# SchlafKindleinSchlaf.net
KiCad netlist of a schematic drawn in EAGLE
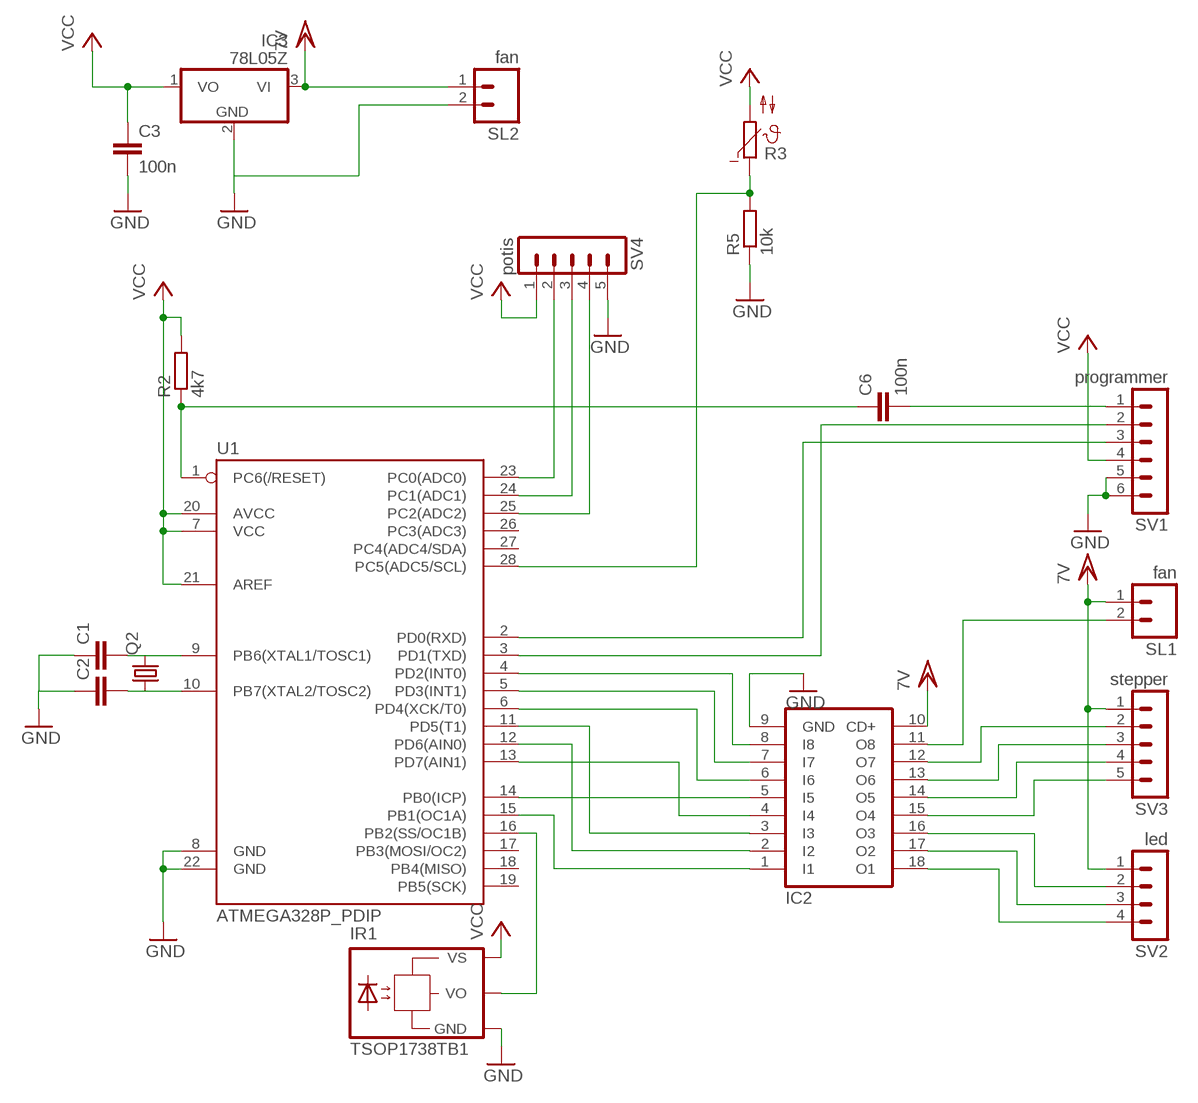
[diagram p0: schematic, sheet 1]

(export (version "E")
  (design (tool "Eeschema 10.0.6"))
  (components
    (comp (ref "C1")
      (value "C2.5/2")
      (footprint "eagle-import:C2.5-2")
      (libsource (lib "eagle-import") (part "C2.5/2"))
    )
    (comp (ref "C2")
      (value "C2.5/2")
      (footprint "eagle-import:C2.5-2")
      (libsource (lib "eagle-import") (part "C2.5/2"))
    )
    (comp (ref "C3")
      (value "100n")
      (footprint "eagle-import:C2.5-2")
      (libsource (lib "eagle-import") (part "C2.5/2"))
    )
    (comp (ref "C6")
      (value "100n")
      (footprint "eagle-import:C2.5-2")
      (libsource (lib "eagle-import") (part "C2.5/2"))
    )
    (comp (ref "IC2")
      (value "ULN2803A")
      (footprint "eagle-import:DIL18")
      (libsource (lib "eagle-import") (part "ULN2803A"))
    )
    (comp (ref "IC3")
      (value "78L05Z")
      (footprint "eagle-import:TO92")
      (libsource (lib "eagle-import") (part "78ZL05"))
    )
    (comp (ref "IR1")
      (value "TSOP1738TB1")
      (footprint "eagle-import:TSOP17_TB1")
      (libsource (lib "eagle-import") (part "TSOP17TB138"))
    )
    (comp (ref "Q2")
      (value "CRYSTALHC49S")
      (footprint "eagle-import:HC49_S")
      (libsource (lib "eagle-import") (part "CRYSTALHC49S"))
    )
    (comp (ref "R2")
      (value "4k7")
      (footprint "eagle-import:0207_7")
      (libsource (lib "eagle-import") (part "R-EU_0207/7"))
    )
    (comp (ref "R3")
      (value "NTC640")
      (footprint "eagle-import:P640")
      (libsource (lib "eagle-import") (part "NTC640"))
    )
    (comp (ref "R5")
      (value "10k")
      (footprint "eagle-import:0207_7")
      (libsource (lib "eagle-import") (part "R-EU_0207/7"))
    )
    (comp (ref "SL1")
      (value "fan")
      (footprint "eagle-import:02PA")
      (libsource (lib "eagle-import") (part "MA02"))
    )
    (comp (ref "SL2")
      (value "fan")
      (footprint "eagle-import:02PA")
      (libsource (lib "eagle-import") (part "MA02"))
    )
    (comp (ref "SV1")
      (value "programmer")
      (footprint "eagle-import:MA06-1")
      (libsource (lib "eagle-import") (part "MA06-1"))
    )
    (comp (ref "SV2")
      (value "led")
      (footprint "eagle-import:MA04-1")
      (libsource (lib "eagle-import") (part "MA04-1"))
    )
    (comp (ref "SV3")
      (value "stepper")
      (footprint "eagle-import:MA05-1")
      (libsource (lib "eagle-import") (part "MA05-1"))
    )
    (comp (ref "SV4")
      (value "potis")
      (footprint "eagle-import:MA05-1")
      (libsource (lib "eagle-import") (part "MA05-1"))
    )
    (comp (ref "U1")
      (value "ATMEGA328P_PDIP")
      (footprint "eagle-import:DIL28-3")
      (libsource (lib "eagle-import") (part "ATMEGA328P_PDIP"))
    )
  )
  (nets
    (net (code "1") (name "7V") (class "Default")
      (node (ref "IC2") (pin "10") (pinfunction "CD+_10") (pintype "passive"))
      (node (ref "IC3") (pin "3") (pinfunction "VI_3") (pintype "input"))
      (node (ref "SL1") (pin "1") (pinfunction "1_1") (pintype "passive"))
      (node (ref "SL2") (pin "1") (pinfunction "1_1") (pintype "passive"))
      (node (ref "SV2") (pin "1") (pinfunction "1_1") (pintype "passive"))
      (node (ref "SV3") (pin "1") (pinfunction "1_1") (pintype "passive"))
    )
    (net (code "2") (name "GND") (class "Default")
      (node (ref "C1") (pin "1") (pinfunction "1_1") (pintype "passive"))
      (node (ref "C2") (pin "1") (pinfunction "1_1") (pintype "passive"))
      (node (ref "C3") (pin "2") (pinfunction "2_2") (pintype "passive"))
      (node (ref "IC2") (pin "9") (pinfunction "GND_9") (pintype "power_in"))
      (node (ref "IC3") (pin "2") (pinfunction "GND_2") (pintype "passive"))
      (node (ref "IR1") (pin "GND") (pinfunction "GND_GND") (pintype "power_in"))
      (node (ref "R5") (pin "1") (pinfunction "1_1") (pintype "passive"))
      (node (ref "SL2") (pin "2") (pinfunction "2_2") (pintype "passive"))
      (node (ref "SV1") (pin "5") (pinfunction "5_5") (pintype "passive"))
      (node (ref "SV1") (pin "6") (pinfunction "6_6") (pintype "passive"))
      (node (ref "SV4") (pin "5") (pinfunction "5_5") (pintype "passive"))
      (node (ref "U1") (pin "22") (pinfunction "GND_22") (pintype "bidirectional"))
      (node (ref "U1") (pin "8") (pinfunction "GND_8") (pintype "bidirectional"))
    )
    (net (code "3") (name "Net-(C6-Pad2)") (class "Default")
      (node (ref "C6") (pin "2") (pinfunction "2_2") (pintype "passive"))
      (node (ref "SV1") (pin "1") (pinfunction "1_1") (pintype "passive"))
    )
    (net (code "4") (name "Net-(IC2-I1)") (class "Default")
      (node (ref "IC2") (pin "1") (pinfunction "I1_1") (pintype "input"))
      (node (ref "U1") (pin "15") (pinfunction "PB1(OC1A)_15") (pintype "bidirectional"))
    )
    (net (code "5") (name "Net-(IC2-I2)") (class "Default")
      (node (ref "IC2") (pin "2") (pinfunction "I2_2") (pintype "input"))
      (node (ref "U1") (pin "12") (pinfunction "PD6(AIN0)_12") (pintype "bidirectional"))
    )
    (net (code "6") (name "Net-(IC2-I3)") (class "Default")
      (node (ref "IC2") (pin "3") (pinfunction "I3_3") (pintype "input"))
      (node (ref "U1") (pin "11") (pinfunction "PD5(T1)_11") (pintype "bidirectional"))
    )
    (net (code "7") (name "Net-(IC2-I4)") (class "Default")
      (node (ref "IC2") (pin "4") (pinfunction "I4_4") (pintype "input"))
      (node (ref "U1") (pin "13") (pinfunction "PD7(AIN1)_13") (pintype "bidirectional"))
    )
    (net (code "8") (name "Net-(IC2-I5)") (class "Default")
      (node (ref "IC2") (pin "5") (pinfunction "I5_5") (pintype "input"))
      (node (ref "U1") (pin "14") (pinfunction "PB0(ICP)_14") (pintype "bidirectional"))
    )
    (net (code "9") (name "Net-(IC2-I6)") (class "Default")
      (node (ref "IC2") (pin "6") (pinfunction "I6_6") (pintype "input"))
      (node (ref "U1") (pin "6") (pinfunction "PD4(XCK/T0)_6") (pintype "bidirectional"))
    )
    (net (code "10") (name "Net-(IC2-I7)") (class "Default")
      (node (ref "IC2") (pin "7") (pinfunction "I7_7") (pintype "input"))
      (node (ref "U1") (pin "5") (pinfunction "PD3(INT1)_5") (pintype "bidirectional"))
    )
    (net (code "11") (name "Net-(IC2-I8)") (class "Default")
      (node (ref "IC2") (pin "8") (pinfunction "I8_8") (pintype "input"))
      (node (ref "U1") (pin "4") (pinfunction "PD2(INT0)_4") (pintype "bidirectional"))
    )
    (net (code "12") (name "Net-(IC2-O1)") (class "Default")
      (node (ref "IC2") (pin "18") (pinfunction "O1_18") (pintype "open_collector"))
      (node (ref "SV2") (pin "4") (pinfunction "4_4") (pintype "passive"))
    )
    (net (code "13") (name "Net-(IC2-O2)") (class "Default")
      (node (ref "IC2") (pin "17") (pinfunction "O2_17") (pintype "open_collector"))
      (node (ref "SV2") (pin "3") (pinfunction "3_3") (pintype "passive"))
    )
    (net (code "14") (name "Net-(IC2-O3)") (class "Default")
      (node (ref "IC2") (pin "16") (pinfunction "O3_16") (pintype "open_collector"))
      (node (ref "SV2") (pin "2") (pinfunction "2_2") (pintype "passive"))
    )
    (net (code "15") (name "Net-(IC2-O4)") (class "Default")
      (node (ref "IC2") (pin "15") (pinfunction "O4_15") (pintype "open_collector"))
      (node (ref "SV3") (pin "5") (pinfunction "5_5") (pintype "passive"))
    )
    (net (code "16") (name "Net-(IC2-O5)") (class "Default")
      (node (ref "IC2") (pin "14") (pinfunction "O5_14") (pintype "open_collector"))
      (node (ref "SV3") (pin "4") (pinfunction "4_4") (pintype "passive"))
    )
    (net (code "17") (name "Net-(IC2-O6)") (class "Default")
      (node (ref "IC2") (pin "13") (pinfunction "O6_13") (pintype "open_collector"))
      (node (ref "SV3") (pin "3") (pinfunction "3_3") (pintype "passive"))
    )
    (net (code "18") (name "Net-(IC2-O7)") (class "Default")
      (node (ref "IC2") (pin "12") (pinfunction "O7_12") (pintype "open_collector"))
      (node (ref "SV3") (pin "2") (pinfunction "2_2") (pintype "passive"))
    )
    (net (code "19") (name "Net-(IC2-O8)") (class "Default")
      (node (ref "IC2") (pin "11") (pinfunction "O8_11") (pintype "open_collector"))
      (node (ref "SL1") (pin "2") (pinfunction "2_2") (pintype "passive"))
    )
    (net (code "20") (name "Net-(U1-PB2(SS{slash}OC1B))") (class "Default")
      (node (ref "IR1") (pin "VO") (pinfunction "VO_VO") (pintype "open_collector"))
      (node (ref "U1") (pin "16") (pinfunction "PB2(SS/OC1B)_16") (pintype "bidirectional"))
    )
    (net (code "21") (name "Net-(U1-PB6(XTAL1{slash}TOSC1))") (class "Default")
      (node (ref "C1") (pin "2") (pinfunction "2_2") (pintype "passive"))
      (node (ref "Q2") (pin "2") (pinfunction "2_2") (pintype "passive"))
      (node (ref "U1") (pin "9") (pinfunction "PB6(XTAL1/TOSC1)_9") (pintype "bidirectional"))
    )
    (net (code "22") (name "Net-(U1-PB7(XTAL2{slash}TOSC2))") (class "Default")
      (node (ref "C2") (pin "2") (pinfunction "2_2") (pintype "passive"))
      (node (ref "Q2") (pin "1") (pinfunction "1_1") (pintype "passive"))
      (node (ref "U1") (pin "10") (pinfunction "PB7(XTAL2/TOSC2)_10") (pintype "bidirectional"))
    )
    (net (code "23") (name "Net-(U1-PC0(ADC0))") (class "Default")
      (node (ref "SV4") (pin "2") (pinfunction "2_2") (pintype "passive"))
      (node (ref "U1") (pin "23") (pinfunction "PC0(ADC0)_23") (pintype "bidirectional"))
    )
    (net (code "24") (name "Net-(U1-PC1(ADC1))") (class "Default")
      (node (ref "SV4") (pin "3") (pinfunction "3_3") (pintype "passive"))
      (node (ref "U1") (pin "24") (pinfunction "PC1(ADC1)_24") (pintype "bidirectional"))
    )
    (net (code "25") (name "Net-(U1-PC2(ADC2))") (class "Default")
      (node (ref "SV4") (pin "4") (pinfunction "4_4") (pintype "passive"))
      (node (ref "U1") (pin "25") (pinfunction "PC2(ADC2)_25") (pintype "bidirectional"))
    )
    (net (code "26") (name "Net-(U1-PC5(ADC5{slash}SCL))") (class "Default")
      (node (ref "R3") (pin "1") (pinfunction "1_1") (pintype "passive"))
      (node (ref "R5") (pin "2") (pinfunction "2_2") (pintype "passive"))
      (node (ref "U1") (pin "28") (pinfunction "PC5(ADC5/SCL)_28") (pintype "bidirectional"))
    )
    (net (code "27") (name "Net-(U1-PC6({slash}RESET))") (class "Default")
      (node (ref "C6") (pin "1") (pinfunction "1_1") (pintype "passive"))
      (node (ref "R2") (pin "1") (pinfunction "1_1") (pintype "passive"))
      (node (ref "U1") (pin "1") (pinfunction "PC6(/RESET)_1") (pintype "bidirectional"))
    )
    (net (code "28") (name "Net-(U1-PD0(RXD))") (class "Default")
      (node (ref "SV1") (pin "3") (pinfunction "3_3") (pintype "passive"))
      (node (ref "U1") (pin "2") (pinfunction "PD0(RXD)_2") (pintype "bidirectional"))
    )
    (net (code "29") (name "Net-(U1-PD1(TXD))") (class "Default")
      (node (ref "SV1") (pin "2") (pinfunction "2_2") (pintype "passive"))
      (node (ref "U1") (pin "3") (pinfunction "PD1(TXD)_3") (pintype "bidirectional"))
    )
    (net (code "30") (name "VCC") (class "Default")
      (node (ref "C3") (pin "1") (pinfunction "1_1") (pintype "passive"))
      (node (ref "IC3") (pin "1") (pinfunction "VO_1") (pintype "passive"))
      (node (ref "IR1") (pin "VS") (pinfunction "VS_VS") (pintype "power_in"))
      (node (ref "R2") (pin "2") (pinfunction "2_2") (pintype "passive"))
      (node (ref "R3") (pin "2") (pinfunction "2_2") (pintype "passive"))
      (node (ref "SV1") (pin "4") (pinfunction "4_4") (pintype "passive"))
      (node (ref "SV4") (pin "1") (pinfunction "1_1") (pintype "passive"))
      (node (ref "U1") (pin "20") (pinfunction "AVCC_20") (pintype "bidirectional"))
      (node (ref "U1") (pin "21") (pinfunction "AREF_21") (pintype "bidirectional"))
      (node (ref "U1") (pin "7") (pinfunction "VCC_7") (pintype "bidirectional"))
    )
    (net (code "31") (name "unconnected-(U1-PB3(MOSI{slash}OC2)-Pad17)") (class "Default")
      (node (ref "U1") (pin "17") (pinfunction "PB3(MOSI/OC2)_17") (pintype "bidirectional"))
    )
    (net (code "32") (name "unconnected-(U1-PB4(MISO)-Pad18)") (class "Default")
      (node (ref "U1") (pin "18") (pinfunction "PB4(MISO)_18") (pintype "bidirectional"))
    )
    (net (code "33") (name "unconnected-(U1-PB5(SCK)-Pad19)") (class "Default")
      (node (ref "U1") (pin "19") (pinfunction "PB5(SCK)_19") (pintype "bidirectional"))
    )
    (net (code "34") (name "unconnected-(U1-PC3(ADC3)-Pad26)") (class "Default")
      (node (ref "U1") (pin "26") (pinfunction "PC3(ADC3)_26") (pintype "bidirectional"))
    )
    (net (code "35") (name "unconnected-(U1-PC4(ADC4{slash}SDA)-Pad27)") (class "Default")
      (node (ref "U1") (pin "27") (pinfunction "PC4(ADC4/SDA)_27") (pintype "bidirectional"))
    )
  )
)
